# usb_card_only.net
KiCad netlist of a schematic drawn in EAGLE
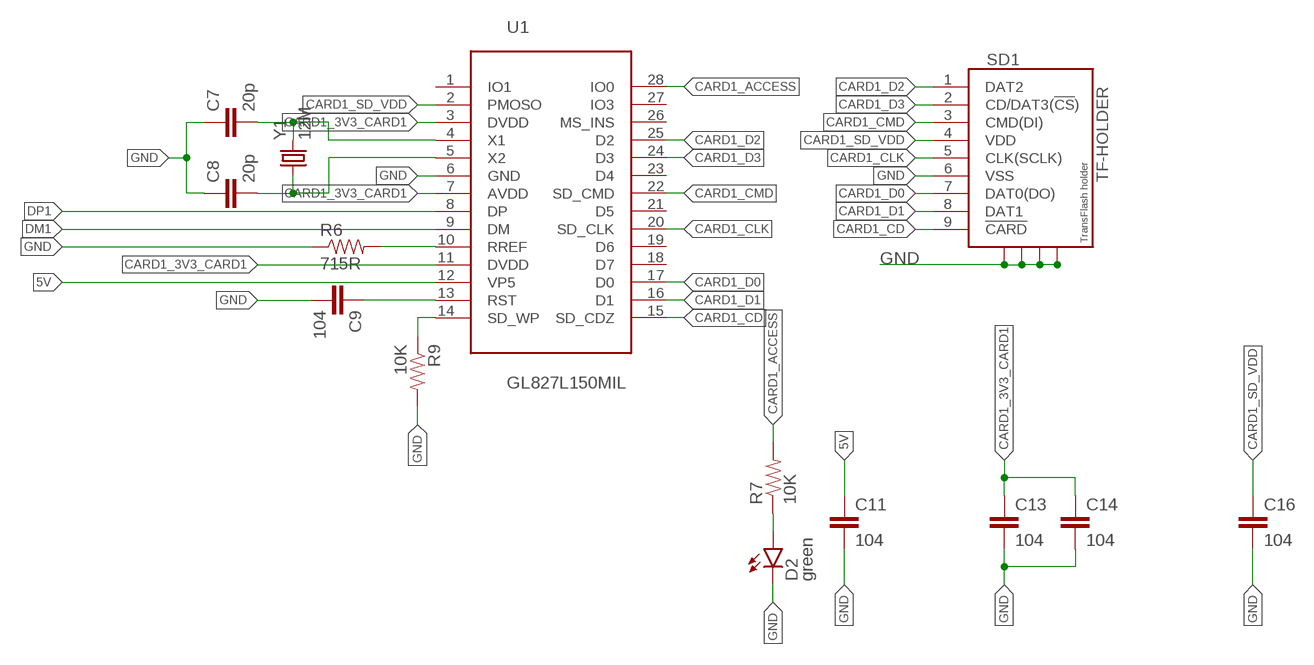
[diagram p0: schematic, sheet 1]

(export (version "E")
  (design (tool "Eeschema 10.0.6"))
  (components
    (comp (ref "C7")
      (value "20p")
      (footprint "eagle-import:1206")
      (libsource (lib "eagle-import") (part "CAP1206"))
    )
    (comp (ref "C8")
      (value "20p")
      (footprint "eagle-import:1206")
      (libsource (lib "eagle-import") (part "CAP1206"))
    )
    (comp (ref "C9")
      (value "104")
      (footprint "eagle-import:1206")
      (libsource (lib "eagle-import") (part "CAP1206"))
    )
    (comp (ref "C11")
      (value "104")
      (footprint "eagle-import:1206")
      (libsource (lib "eagle-import") (part "CAP1206"))
    )
    (comp (ref "C13")
      (value "104")
      (footprint "eagle-import:1206")
      (libsource (lib "eagle-import") (part "CAP1206"))
    )
    (comp (ref "C14")
      (value "104")
      (footprint "eagle-import:1206")
      (libsource (lib "eagle-import") (part "CAP1206"))
    )
    (comp (ref "C16")
      (value "104")
      (footprint "eagle-import:1206")
      (libsource (lib "eagle-import") (part "CAP1206"))
    )
    (comp (ref "D2")
      (value "green")
      (footprint "eagle-import:LED-1206")
      (libsource (lib "eagle-import") (part "LED1206"))
    )
    (comp (ref "R6")
      (value "715R")
      (footprint "eagle-import:1206")
      (libsource (lib "eagle-import") (part "RESISTOR1206"))
    )
    (comp (ref "R7")
      (value "10K")
      (footprint "eagle-import:1206")
      (libsource (lib "eagle-import") (part "RESISTOR1206"))
    )
    (comp (ref "R9")
      (value "10K")
      (footprint "eagle-import:1206")
      (libsource (lib "eagle-import") (part "RESISTOR1206"))
    )
    (comp (ref "SD1")
      (value "TF-HOLDER")
      (footprint "eagle-import:TF-PULL")
      (libsource (lib "eagle-import") (part "TF-HOLDER"))
    )
    (comp (ref "U1")
      (value "GL827L150MIL")
      (footprint "eagle-import:SSOP28-39")
      (libsource (lib "eagle-import") (part "GL827L150MIL"))
    )
    (comp (ref "Y1")
      (value "12M")
      (footprint "eagle-import:HC49US")
      (libsource (lib "eagle-import") (part "CRYSTAL2HC49US"))
    )
  )
  (nets
    (net (code "1") (name "5V") (class "Default")
      (node (ref "C11") (pin "1") (pinfunction "1_1") (pintype "passive"))
      (node (ref "U1") (pin "12") (pinfunction "VP5_12") (pintype "bidirectional"))
    )
    (net (code "2") (name "CARD1_3V3_CARD1") (class "Default")
      (node (ref "C13") (pin "1") (pinfunction "1_1") (pintype "passive"))
      (node (ref "C14") (pin "1") (pinfunction "1_1") (pintype "passive"))
      (node (ref "U1") (pin "11") (pinfunction "DVDD_11") (pintype "bidirectional"))
      (node (ref "U1") (pin "3") (pinfunction "DVDD_3") (pintype "bidirectional"))
      (node (ref "U1") (pin "7") (pinfunction "AVDD_7") (pintype "bidirectional"))
    )
    (net (code "3") (name "CARD1_ACCESS") (class "Default")
      (node (ref "R7") (pin "2") (pinfunction "2_2") (pintype "passive"))
      (node (ref "U1") (pin "28") (pinfunction "IO0_28") (pintype "bidirectional"))
    )
    (net (code "4") (name "CARD1_CD") (class "Default")
      (node (ref "SD1") (pin "9") (pinfunction "~{CARD}_9") (pintype "passive"))
      (node (ref "U1") (pin "15") (pinfunction "SD_CDZ_15") (pintype "bidirectional"))
    )
    (net (code "5") (name "CARD1_CLK") (class "Default")
      (node (ref "SD1") (pin "5") (pinfunction "CLK(SCLK)_5") (pintype "input"))
      (node (ref "U1") (pin "20") (pinfunction "SD_CLK_20") (pintype "bidirectional"))
    )
    (net (code "6") (name "CARD1_CMD") (class "Default")
      (node (ref "SD1") (pin "3") (pinfunction "CMD(DI)_3") (pintype "bidirectional"))
      (node (ref "U1") (pin "22") (pinfunction "SD_CMD_22") (pintype "bidirectional"))
    )
    (net (code "7") (name "CARD1_D0") (class "Default")
      (node (ref "SD1") (pin "7") (pinfunction "DAT0(DO)_7") (pintype "bidirectional"))
      (node (ref "U1") (pin "17") (pinfunction "D0_17") (pintype "bidirectional"))
    )
    (net (code "8") (name "CARD1_D1") (class "Default")
      (node (ref "SD1") (pin "8") (pinfunction "DAT1_8") (pintype "bidirectional"))
      (node (ref "U1") (pin "16") (pinfunction "D1_16") (pintype "bidirectional"))
    )
    (net (code "9") (name "CARD1_D2") (class "Default")
      (node (ref "SD1") (pin "1") (pinfunction "DAT2_1") (pintype "bidirectional"))
      (node (ref "U1") (pin "25") (pinfunction "D2_25") (pintype "bidirectional"))
    )
    (net (code "10") (name "CARD1_D3") (class "Default")
      (node (ref "SD1") (pin "2") (pinfunction "CD/DAT3(~{CS})_2") (pintype "bidirectional"))
      (node (ref "U1") (pin "24") (pinfunction "D3_24") (pintype "bidirectional"))
    )
    (net (code "11") (name "CARD1_SD_VDD") (class "Default")
      (node (ref "C16") (pin "1") (pinfunction "1_1") (pintype "passive"))
      (node (ref "SD1") (pin "4") (pinfunction "VDD_4") (pintype "power_in"))
      (node (ref "U1") (pin "2") (pinfunction "PMOSO_2") (pintype "bidirectional"))
    )
    (net (code "12") (name "DM1") (class "Default")
      (node (ref "U1") (pin "9") (pinfunction "DM_9") (pintype "bidirectional"))
    )
    (net (code "13") (name "DP1") (class "Default")
      (node (ref "U1") (pin "8") (pinfunction "DP_8") (pintype "bidirectional"))
    )
    (net (code "14") (name "GND") (class "Default")
      (node (ref "C11") (pin "2") (pinfunction "2_2") (pintype "passive"))
      (node (ref "C13") (pin "2") (pinfunction "2_2") (pintype "passive"))
      (node (ref "C14") (pin "2") (pinfunction "2_2") (pintype "passive"))
      (node (ref "C16") (pin "2") (pinfunction "2_2") (pintype "passive"))
      (node (ref "C7") (pin "1") (pinfunction "1_1") (pintype "passive"))
      (node (ref "C8") (pin "1") (pinfunction "1_1") (pintype "passive"))
      (node (ref "C9") (pin "2") (pinfunction "2_2") (pintype "passive"))
      (node (ref "D2") (pin "C") (pinfunction "C_C") (pintype "passive"))
      (node (ref "R6") (pin "1") (pinfunction "1_1") (pintype "passive"))
      (node (ref "R9") (pin "2") (pinfunction "2_2") (pintype "passive"))
      (node (ref "SD1") (pin "6") (pinfunction "VSS_6") (pintype "power_in"))
      (node (ref "SD1") (pin "S1") (pinfunction "S1_S1") (pintype "passive"))
      (node (ref "SD1") (pin "S2") (pinfunction "S2_S2") (pintype "passive"))
      (node (ref "SD1") (pin "S3") (pinfunction "S3_S3") (pintype "passive"))
      (node (ref "SD1") (pin "S4") (pinfunction "S4_S4") (pintype "passive"))
      (node (ref "U1") (pin "6") (pinfunction "GND_6") (pintype "bidirectional"))
    )
    (net (code "15") (name "Net-(D2-PadA)") (class "Default")
      (node (ref "D2") (pin "A") (pinfunction "A_A") (pintype "passive"))
      (node (ref "R7") (pin "1") (pinfunction "1_1") (pintype "passive"))
    )
    (net (code "16") (name "Net-(U1-RREF)") (class "Default")
      (node (ref "R6") (pin "2") (pinfunction "2_2") (pintype "passive"))
      (node (ref "U1") (pin "10") (pinfunction "RREF_10") (pintype "bidirectional"))
    )
    (net (code "17") (name "Net-(U1-RST)") (class "Default")
      (node (ref "C9") (pin "1") (pinfunction "1_1") (pintype "passive"))
      (node (ref "U1") (pin "13") (pinfunction "RST_13") (pintype "bidirectional"))
    )
    (net (code "18") (name "Net-(U1-SD_WP)") (class "Default")
      (node (ref "R9") (pin "1") (pinfunction "1_1") (pintype "passive"))
      (node (ref "U1") (pin "14") (pinfunction "SD_WP_14") (pintype "bidirectional"))
    )
    (net (code "19") (name "Net-(U1-X1)") (class "Default")
      (node (ref "C7") (pin "2") (pinfunction "2_2") (pintype "passive"))
      (node (ref "U1") (pin "4") (pinfunction "X1_4") (pintype "bidirectional"))
      (node (ref "Y1") (pin "2") (pinfunction "2_2") (pintype "passive"))
    )
    (net (code "20") (name "Net-(U1-X2)") (class "Default")
      (node (ref "C8") (pin "2") (pinfunction "2_2") (pintype "passive"))
      (node (ref "U1") (pin "5") (pinfunction "X2_5") (pintype "bidirectional"))
      (node (ref "Y1") (pin "1") (pinfunction "1_1") (pintype "passive"))
    )
    (net (code "21") (name "unconnected-(U1-D4-Pad23)") (class "Default")
      (node (ref "U1") (pin "23") (pinfunction "D4_23") (pintype "bidirectional"))
    )
    (net (code "22") (name "unconnected-(U1-D5-Pad21)") (class "Default")
      (node (ref "U1") (pin "21") (pinfunction "D5_21") (pintype "bidirectional"))
    )
    (net (code "23") (name "unconnected-(U1-D6-Pad19)") (class "Default")
      (node (ref "U1") (pin "19") (pinfunction "D6_19") (pintype "bidirectional"))
    )
    (net (code "24") (name "unconnected-(U1-D7-Pad18)") (class "Default")
      (node (ref "U1") (pin "18") (pinfunction "D7_18") (pintype "bidirectional"))
    )
    (net (code "25") (name "unconnected-(U1-IO1-Pad1)") (class "Default")
      (node (ref "U1") (pin "1") (pinfunction "IO1_1") (pintype "bidirectional"))
    )
    (net (code "26") (name "unconnected-(U1-IO3-Pad27)") (class "Default")
      (node (ref "U1") (pin "27") (pinfunction "IO3_27") (pintype "bidirectional"))
    )
    (net (code "27") (name "unconnected-(U1-MS_INS-Pad26)") (class "Default")
      (node (ref "U1") (pin "26") (pinfunction "MS_INS_26") (pintype "bidirectional"))
    )
  )
)
